# Elect_5pulgadas_v1.net
KiCad netlist of a schematic drawn in EAGLE
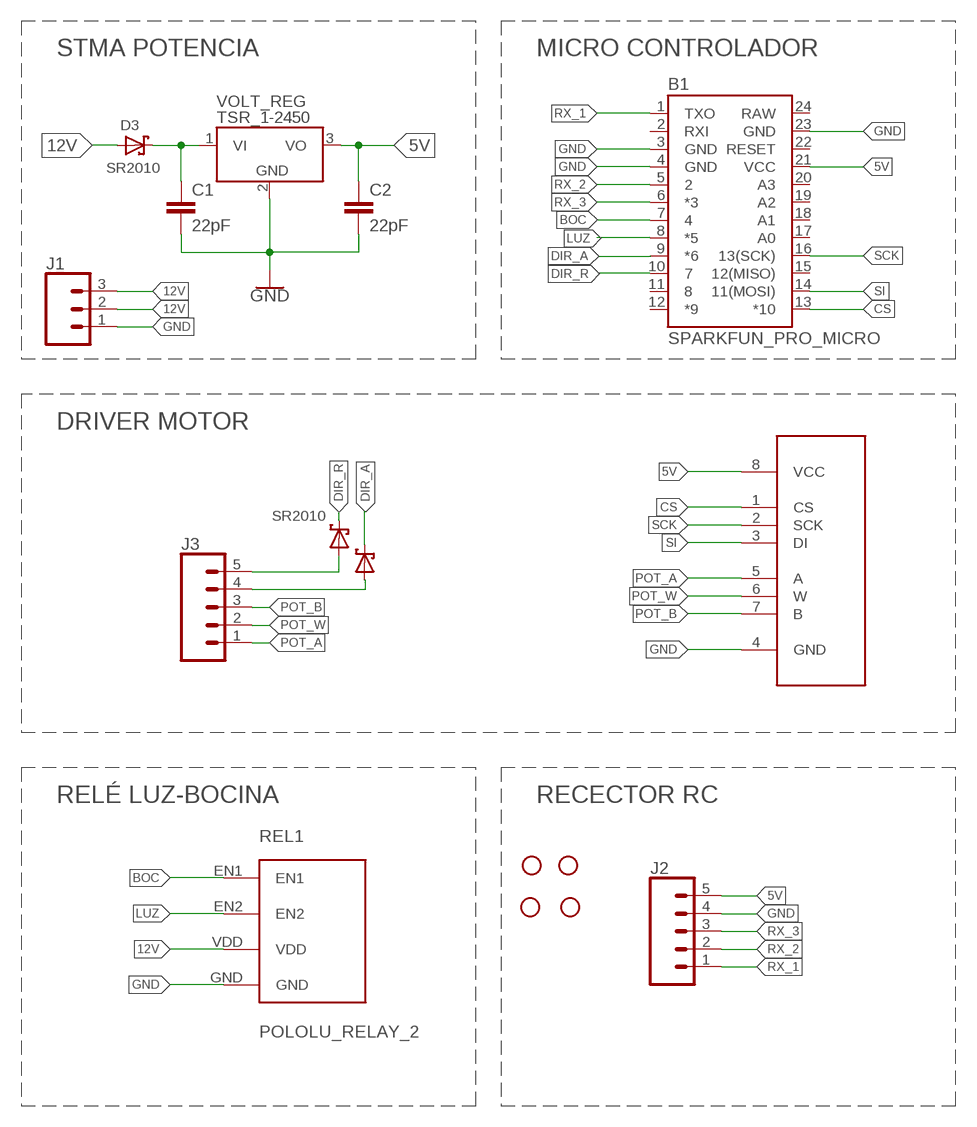
[diagram p0: schematic, sheet 1]

(export (version "E")
  (design (tool "Eeschema 10.0.6"))
  (components
    (comp (ref "B1")
      (value "SPARKFUN_PRO_MICRO")
      (footprint "eagle-import:SPARKFUN_PRO_MICRO")
      (libsource (lib "eagle-import") (part "SPARKFUN_PRO_MICRO"))
    )
    (comp (ref "C1")
      (value "22pF")
      (footprint "eagle-import:CAP-PTH-SMALL-KIT")
      (libsource (lib "eagle-import") (part "0.1UF-KIT-EZ-50V-20%"))
    )
    (comp (ref "C2")
      (value "22pF")
      (footprint "eagle-import:CAP-PTH-SMALL-KIT")
      (libsource (lib "eagle-import") (part "0.1UF-KIT-EZ-50V-20%"))
    )
    (comp (ref "D1")
      (value "SR2010")
      (footprint "eagle-import:DO41-7.6")
      (libsource (lib "eagle-import") (part "1N5817-B"))
    )
    (comp (ref "D2")
      (value "SR2010")
      (footprint "eagle-import:DO41-7.6")
      (libsource (lib "eagle-import") (part "1N5817-B"))
    )
    (comp (ref "D3")
      (value "SR2010")
      (footprint "eagle-import:DO41-7.6")
      (libsource (lib "eagle-import") (part "1N5817-B"))
    )
    (comp (ref "H1")
      (value "STAND-OFF")
      (footprint "eagle-import:STAND-OFF")
      (libsource (lib "eagle-import") (part "STAND-OFF"))
    )
    (comp (ref "H2")
      (value "STAND-OFF")
      (footprint "eagle-import:STAND-OFF")
      (libsource (lib "eagle-import") (part "STAND-OFF"))
    )
    (comp (ref "H3")
      (value "STAND-OFF")
      (footprint "eagle-import:STAND-OFF")
      (libsource (lib "eagle-import") (part "STAND-OFF"))
    )
    (comp (ref "H4")
      (value "STAND-OFF")
      (footprint "eagle-import:STAND-OFF")
      (libsource (lib "eagle-import") (part "STAND-OFF"))
    )
    (comp (ref "J1")
      (value "CONN_03-SCREW-5MM")
      (footprint "eagle-import:SCREWTERMINAL-5MM-3")
      (libsource (lib "eagle-import") (part "CONN_03-SCREW-5MM"))
    )
    (comp (ref "J2")
      (value "CONN_05")
      (footprint "eagle-import:1X05")
      (libsource (lib "eagle-import") (part "CONN_05"))
    )
    (comp (ref "J3")
      (value "CONN_05")
      (footprint "eagle-import:1X05")
      (libsource (lib "eagle-import") (part "CONN_05"))
    )
    (comp (ref "REL1")
      (value "POLOLU_RELAY_2")
      (footprint "eagle-import:POLOLU_RELAY_2")
      (libsource (lib "eagle-import") (part "POLOLU_RELAY_2"))
    )
    (comp (ref "U1")
      (value "MCP41XXX")
      (footprint "eagle-import:DIP08")
      (libsource (lib "eagle-import") (part "MCP41XXXDIL"))
    )
    (comp (ref "VOLT_REG")
      (value "TSR_1-2450")
      (footprint "eagle-import:TSR-1")
      (libsource (lib "eagle-import") (part "TSR_1-2450"))
    )
  )
  (nets
    (net (code "1") (name "/RAW") (class "Default")
      (node (ref "B1") (pin "24") (pinfunction "RAW_24") (pintype "power_in"))
    )
    (net (code "2") (name "5V") (class "Default")
      (node (ref "B1") (pin "21") (pinfunction "VCC_21") (pintype "power_in"))
      (node (ref "C2") (pin "1") (pinfunction "1_1") (pintype "passive"))
      (node (ref "J2") (pin "5") (pinfunction "5_5") (pintype "passive"))
      (node (ref "U1") (pin "8") (pinfunction "VCC_8") (pintype "bidirectional"))
      (node (ref "VOLT_REG") (pin "3") (pinfunction "VO_3") (pintype "power_in"))
    )
    (net (code "3") (name "12V") (class "Default")
      (node (ref "D3") (pin "A") (pinfunction "A_A") (pintype "passive"))
      (node (ref "J1") (pin "2") (pinfunction "2_2") (pintype "passive"))
      (node (ref "J1") (pin "3") (pinfunction "3_3") (pintype "passive"))
      (node (ref "REL1") (pin "VDD") (pinfunction "VDD_VDD") (pintype "bidirectional"))
    )
    (net (code "4") (name "BOC") (class "Default")
      (node (ref "B1") (pin "7") (pinfunction "4_7") (pintype "bidirectional"))
      (node (ref "REL1") (pin "EN1") (pinfunction "EN1_EN1") (pintype "bidirectional"))
    )
    (net (code "5") (name "CS") (class "Default")
      (node (ref "B1") (pin "13") (pinfunction "*10_13") (pintype "bidirectional"))
      (node (ref "U1") (pin "1") (pinfunction "CS_1") (pintype "bidirectional"))
    )
    (net (code "6") (name "DIR_A") (class "Default")
      (node (ref "B1") (pin "9") (pinfunction "*6_9") (pintype "bidirectional"))
      (node (ref "D1") (pin "C") (pinfunction "C_C") (pintype "passive"))
    )
    (net (code "7") (name "DIR_R") (class "Default")
      (node (ref "B1") (pin "10") (pinfunction "7_10") (pintype "bidirectional"))
      (node (ref "D2") (pin "C") (pinfunction "C_C") (pintype "passive"))
    )
    (net (code "8") (name "GND") (class "Default")
      (node (ref "B1") (pin "23") (pinfunction "GND_23") (pintype "power_in"))
      (node (ref "B1") (pin "3") (pinfunction "GND_3") (pintype "power_in"))
      (node (ref "B1") (pin "4") (pinfunction "GND_4") (pintype "power_in"))
      (node (ref "C1") (pin "2") (pinfunction "2_2") (pintype "passive"))
      (node (ref "C2") (pin "2") (pinfunction "2_2") (pintype "passive"))
      (node (ref "J1") (pin "1") (pinfunction "1_1") (pintype "passive"))
      (node (ref "J2") (pin "4") (pinfunction "4_4") (pintype "passive"))
      (node (ref "REL1") (pin "GND") (pinfunction "GND_GND") (pintype "bidirectional"))
      (node (ref "U1") (pin "4") (pinfunction "GND_4") (pintype "bidirectional"))
      (node (ref "VOLT_REG") (pin "2") (pinfunction "GND_2") (pintype "power_in"))
    )
    (net (code "9") (name "LUZ") (class "Default")
      (node (ref "B1") (pin "8") (pinfunction "*5_8") (pintype "bidirectional"))
      (node (ref "REL1") (pin "EN2") (pinfunction "EN2_EN2") (pintype "bidirectional"))
    )
    (net (code "10") (name "Net-(D1-PadA)") (class "Default")
      (node (ref "D1") (pin "A") (pinfunction "A_A") (pintype "passive"))
      (node (ref "J3") (pin "4") (pinfunction "4_4") (pintype "passive"))
    )
    (net (code "11") (name "Net-(D2-PadA)") (class "Default")
      (node (ref "D2") (pin "A") (pinfunction "A_A") (pintype "passive"))
      (node (ref "J3") (pin "5") (pinfunction "5_5") (pintype "passive"))
    )
    (net (code "12") (name "Net-(VOLT_REG-VI)") (class "Default")
      (node (ref "C1") (pin "1") (pinfunction "1_1") (pintype "passive"))
      (node (ref "D3") (pin "C") (pinfunction "C_C") (pintype "passive"))
      (node (ref "VOLT_REG") (pin "1") (pinfunction "VI_1") (pintype "power_in"))
    )
    (net (code "13") (name "POT_A") (class "Default")
      (node (ref "J3") (pin "1") (pinfunction "1_1") (pintype "passive"))
      (node (ref "U1") (pin "5") (pinfunction "A_5") (pintype "bidirectional"))
    )
    (net (code "14") (name "POT_B") (class "Default")
      (node (ref "J3") (pin "3") (pinfunction "3_3") (pintype "passive"))
      (node (ref "U1") (pin "7") (pinfunction "B_7") (pintype "bidirectional"))
    )
    (net (code "15") (name "POT_W") (class "Default")
      (node (ref "J3") (pin "2") (pinfunction "2_2") (pintype "passive"))
      (node (ref "U1") (pin "6") (pinfunction "W_6") (pintype "bidirectional"))
    )
    (net (code "16") (name "RX_1") (class "Default")
      (node (ref "B1") (pin "1") (pinfunction "TXO_1") (pintype "bidirectional"))
      (node (ref "J2") (pin "1") (pinfunction "1_1") (pintype "passive"))
    )
    (net (code "17") (name "RX_2") (class "Default")
      (node (ref "B1") (pin "5") (pinfunction "2_5") (pintype "bidirectional"))
      (node (ref "J2") (pin "2") (pinfunction "2_2") (pintype "passive"))
    )
    (net (code "18") (name "RX_3") (class "Default")
      (node (ref "B1") (pin "6") (pinfunction "*3_6") (pintype "bidirectional"))
      (node (ref "J2") (pin "3") (pinfunction "3_3") (pintype "passive"))
    )
    (net (code "19") (name "SCK") (class "Default")
      (node (ref "B1") (pin "16") (pinfunction "13(SCK)_16") (pintype "bidirectional"))
      (node (ref "U1") (pin "2") (pinfunction "SCK_2") (pintype "bidirectional"))
    )
    (net (code "20") (name "SI") (class "Default")
      (node (ref "B1") (pin "14") (pinfunction "11(MOSI)_14") (pintype "bidirectional"))
      (node (ref "U1") (pin "3") (pinfunction "DI_3") (pintype "bidirectional"))
    )
    (net (code "21") (name "unconnected-(B1-*9-Pad12)") (class "Default")
      (node (ref "B1") (pin "12") (pinfunction "*9_12") (pintype "bidirectional"))
    )
    (net (code "22") (name "unconnected-(B1-8-Pad11)") (class "Default")
      (node (ref "B1") (pin "11") (pinfunction "8_11") (pintype "bidirectional"))
    )
    (net (code "23") (name "unconnected-(B1-12(MISO)-Pad15)") (class "Default")
      (node (ref "B1") (pin "15") (pinfunction "12(MISO)_15") (pintype "bidirectional"))
    )
    (net (code "24") (name "unconnected-(B1-A0-Pad17)") (class "Default")
      (node (ref "B1") (pin "17") (pinfunction "A0_17") (pintype "bidirectional"))
    )
    (net (code "25") (name "unconnected-(B1-A1-Pad18)") (class "Default")
      (node (ref "B1") (pin "18") (pinfunction "A1_18") (pintype "bidirectional"))
    )
    (net (code "26") (name "unconnected-(B1-A2-Pad19)") (class "Default")
      (node (ref "B1") (pin "19") (pinfunction "A2_19") (pintype "bidirectional"))
    )
    (net (code "27") (name "unconnected-(B1-A3-Pad20)") (class "Default")
      (node (ref "B1") (pin "20") (pinfunction "A3_20") (pintype "bidirectional"))
    )
    (net (code "28") (name "unconnected-(B1-RESET-Pad22)") (class "Default")
      (node (ref "B1") (pin "22") (pinfunction "RESET_22") (pintype "bidirectional"))
    )
    (net (code "29") (name "unconnected-(B1-RXI-Pad2)") (class "Default")
      (node (ref "B1") (pin "2") (pinfunction "RXI_2") (pintype "bidirectional"))
    )
  )
)
